# MCU.net
KiCad netlist of a schematic drawn in Altium Designer
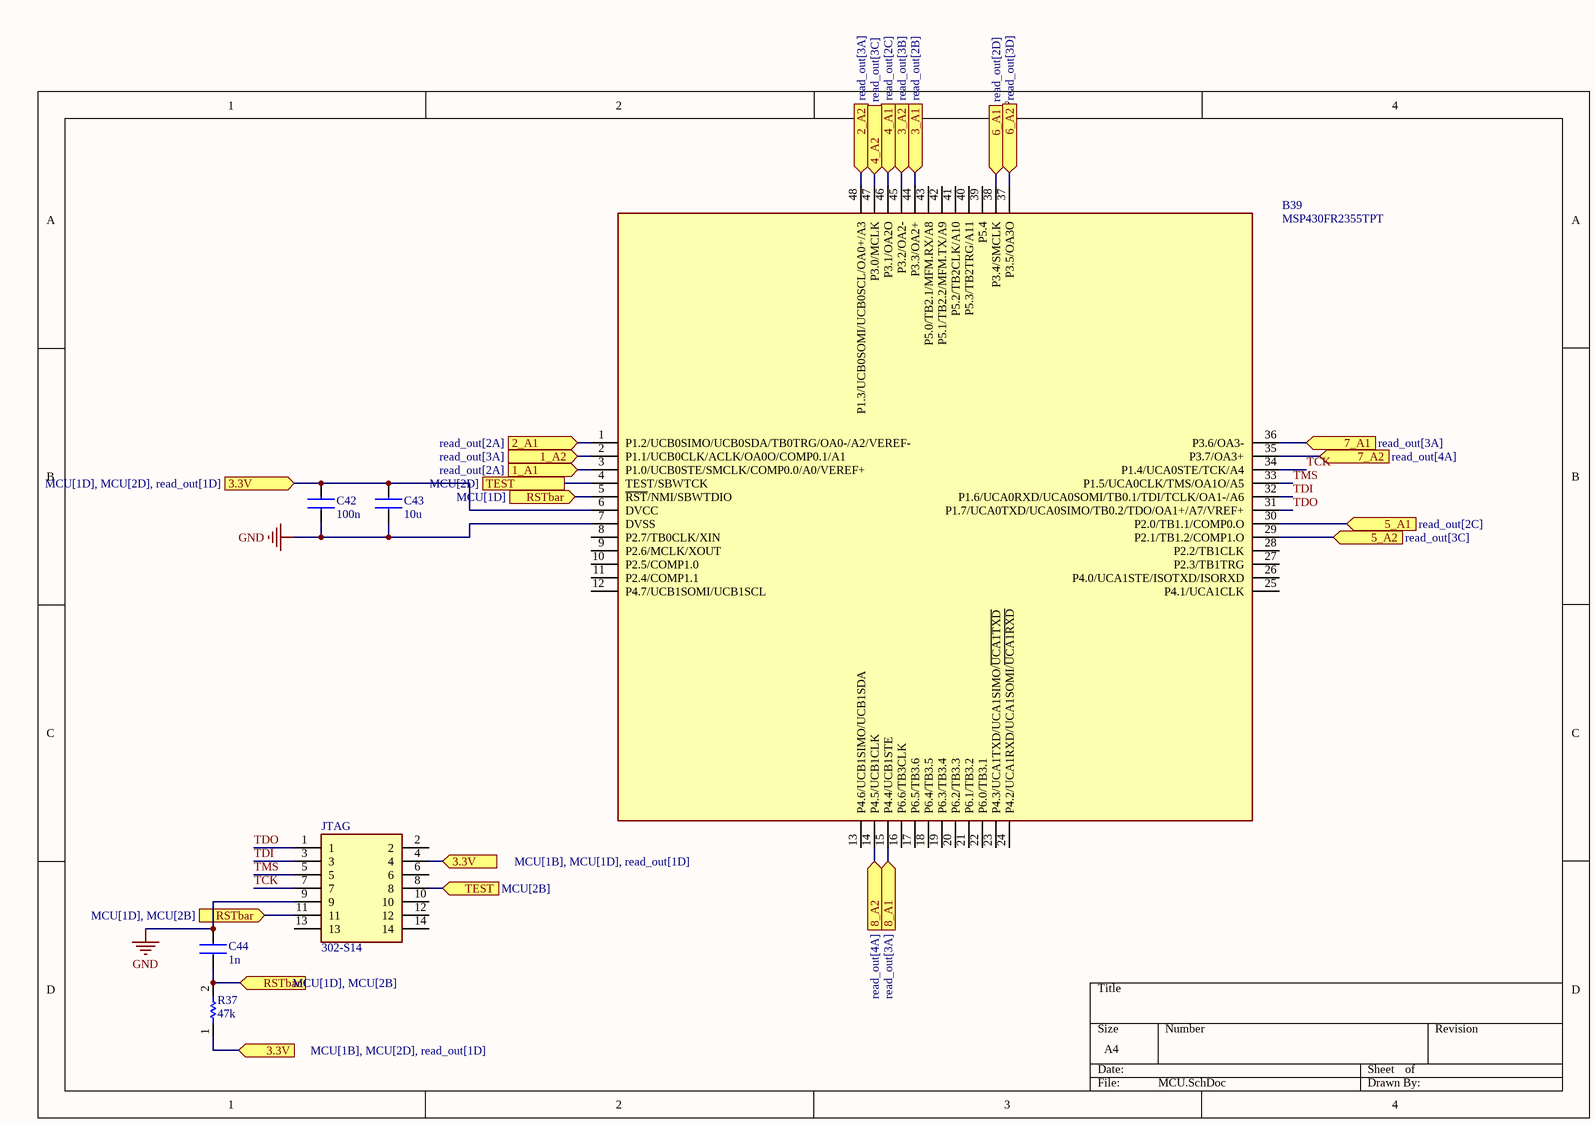
[diagram p0: MCU.SchDoc]

(export (version "E")
  (design (tool "Eeschema 10.0.6"))
  (components
    (comp (ref "B39")
      (value "MSP430FR2355TPT")
      (footprint "QFP50P900X900X160-48N")
      (fields (field (name "MOUSER PART NUMBER") "595-MSP430FR2355TPT"))
      (libsource (lib "Schlib1") (part "MSP430FR2355TPT"))
    )
    (comp (ref "C42")
      (value "100n")
      (footprint "0805X7R106KT1AT")
      (libsource (lib "Schlib1") (part "capacitor"))
    )
    (comp (ref "C43")
      (value "10u")
      (footprint "0805X7R106KT1AT")
      (libsource (lib "Schlib1") (part "capacitor"))
    )
    (comp (ref "C44")
      (value "1n")
      (footprint "0805X7R106KT1AT")
      (libsource (lib "Schlib1") (part "capacitor"))
    )
    (comp (ref "JTAG")
      (value "302-S14")
      (footprint "CONN_7024614xx_MOL")
      (libsource (lib "Schlib1") (part "JTAG"))
    )
    (comp (ref "R37")
      (value "47k")
      (footprint "CR0805-FX-1543ELF")
      (libsource (lib "Schlib1") (part "resistor"))
    )
  )
  (nets
    (net (code "1") (name "/1_A1") (class "Default")
      (node (ref "B39") (pin "3") (pinfunction "P1.0/UCB0STE/SMCLK/COMP0.0/A0/VEREF+_3") (pintype "passive"))
    )
    (net (code "2") (name "/1_A2") (class "Default")
      (node (ref "B39") (pin "2") (pinfunction "P1.1/UCB0CLK/ACLK/OA0O/COMP0.1/A1_2") (pintype "passive"))
    )
    (net (code "3") (name "/2_A1") (class "Default")
      (node (ref "B39") (pin "1") (pinfunction "P1.2/UCB0SIMO/UCB0SDA/TB0TRG/OA0-/A2/VEREF-_1") (pintype "passive"))
    )
    (net (code "4") (name "/2_A2") (class "Default")
      (node (ref "B39") (pin "48") (pinfunction "P1.3/UCB0SOMI/UCB0SCL/OA0+/A3_48") (pintype "passive"))
    )
    (net (code "5") (name "/3.3V") (class "Default")
      (node (ref "B39") (pin "6") (pinfunction "DVCC_6") (pintype "passive"))
      (node (ref "C42") (pin "1") (pinfunction "1_1") (pintype "passive"))
      (node (ref "C43") (pin "1") (pinfunction "1_1") (pintype "passive"))
      (node (ref "JTAG") (pin "4") (pinfunction "4_4") (pintype "passive"))
      (node (ref "R37") (pin "1") (pinfunction "1_1") (pintype "passive"))
    )
    (net (code "6") (name "/3_A1") (class "Default")
      (node (ref "B39") (pin "44") (pinfunction "P3.3/OA2+_44") (pintype "passive"))
    )
    (net (code "7") (name "/3_A2") (class "Default")
      (node (ref "B39") (pin "45") (pinfunction "P3.2/OA2-_45") (pintype "passive"))
    )
    (net (code "8") (name "/4_A1") (class "Default")
      (node (ref "B39") (pin "46") (pinfunction "P3.1/OA2O_46") (pintype "passive"))
    )
    (net (code "9") (name "/4_A2") (class "Default")
      (node (ref "B39") (pin "47") (pinfunction "P3.0/MCLK_47") (pintype "passive"))
    )
    (net (code "10") (name "/5_A1") (class "Default")
      (node (ref "B39") (pin "30") (pinfunction "P2.0/TB1.1/COMP0.O_30") (pintype "passive"))
    )
    (net (code "11") (name "/5_A2") (class "Default")
      (node (ref "B39") (pin "29") (pinfunction "P2.1/TB1.2/COMP1.O_29") (pintype "passive"))
    )
    (net (code "12") (name "/6_A1") (class "Default")
      (node (ref "B39") (pin "38") (pinfunction "P3.4/SMCLK_38") (pintype "passive"))
    )
    (net (code "13") (name "/6_A2") (class "Default")
      (node (ref "B39") (pin "37") (pinfunction "P3.5/OA3O_37") (pintype "passive"))
    )
    (net (code "14") (name "/7_A1") (class "Default")
      (node (ref "B39") (pin "36") (pinfunction "P3.6/OA3-_36") (pintype "passive"))
    )
    (net (code "15") (name "/7_A2") (class "Default")
      (node (ref "B39") (pin "35") (pinfunction "P3.7/OA3+_35") (pintype "passive"))
    )
    (net (code "16") (name "/8_A1") (class "Default")
      (node (ref "B39") (pin "15") (pinfunction "P4.4/UCB1STE_15") (pintype "passive"))
    )
    (net (code "17") (name "/8_A2") (class "Default")
      (node (ref "B39") (pin "14") (pinfunction "P4.5/UCB1CLK_14") (pintype "passive"))
    )
    (net (code "18") (name "/RSTbar") (class "Default")
      (node (ref "B39") (pin "5") (pinfunction "~{RST}/NMI/SBWTDIO_5") (pintype "passive"))
      (node (ref "C44") (pin "1") (pinfunction "1_1") (pintype "passive"))
      (node (ref "JTAG") (pin "11") (pinfunction "11_11") (pintype "passive"))
      (node (ref "R37") (pin "2") (pinfunction "2_2") (pintype "passive"))
    )
    (net (code "19") (name "/TCK") (class "Default")
      (node (ref "B39") (pin "34") (pinfunction "P1.4/UCA0STE/TCK/A4_34") (pintype "passive"))
      (node (ref "JTAG") (pin "7") (pinfunction "7_7") (pintype "passive"))
    )
    (net (code "20") (name "/TDI") (class "Default")
      (node (ref "B39") (pin "32") (pinfunction "P1.6/UCA0RXD/UCA0SOMI/TB0.1/TDI/TCLK/OA1-/A6_32") (pintype "passive"))
      (node (ref "JTAG") (pin "3") (pinfunction "3_3") (pintype "passive"))
    )
    (net (code "21") (name "/TDO") (class "Default")
      (node (ref "B39") (pin "31") (pinfunction "P1.7/UCA0TXD/UCA0SIMO/TB0.2/TDO/OA1+/A7/VREF+_31") (pintype "passive"))
      (node (ref "JTAG") (pin "1") (pinfunction "1_1") (pintype "passive"))
    )
    (net (code "22") (name "/TEST") (class "Default")
      (node (ref "B39") (pin "4") (pinfunction "TEST/SBWTCK_4") (pintype "passive"))
      (node (ref "JTAG") (pin "8") (pinfunction "8_8") (pintype "passive"))
    )
    (net (code "23") (name "/TMS") (class "Default")
      (node (ref "B39") (pin "33") (pinfunction "P1.5/UCA0CLK/TMS/OA1O/A5_33") (pintype "passive"))
      (node (ref "JTAG") (pin "5") (pinfunction "5_5") (pintype "passive"))
    )
    (net (code "24") (name "GND") (class "Default")
      (node (ref "B39") (pin "7") (pinfunction "DVSS_7") (pintype "passive"))
      (node (ref "C42") (pin "2") (pinfunction "2_2") (pintype "passive"))
      (node (ref "C43") (pin "2") (pinfunction "2_2") (pintype "passive"))
      (node (ref "C44") (pin "2") (pinfunction "2_2") (pintype "passive"))
      (node (ref "JTAG") (pin "9") (pinfunction "9_9") (pintype "passive"))
    )
    (net (code "25") (name "unconnected-(B39-P2.2{slash}TB1CLK-Pad28)") (class "Default")
      (node (ref "B39") (pin "28") (pinfunction "P2.2/TB1CLK_28") (pintype "passive"))
    )
    (net (code "26") (name "unconnected-(B39-P2.3{slash}TB1TRG-Pad27)") (class "Default")
      (node (ref "B39") (pin "27") (pinfunction "P2.3/TB1TRG_27") (pintype "passive"))
    )
    (net (code "27") (name "unconnected-(B39-P2.4{slash}COMP1.1-Pad11)") (class "Default")
      (node (ref "B39") (pin "11") (pinfunction "P2.4/COMP1.1_11") (pintype "passive"))
    )
    (net (code "28") (name "unconnected-(B39-P2.5{slash}COMP1.0-Pad10)") (class "Default")
      (node (ref "B39") (pin "10") (pinfunction "P2.5/COMP1.0_10") (pintype "passive"))
    )
    (net (code "29") (name "unconnected-(B39-P2.6{slash}MCLK{slash}XOUT-Pad9)") (class "Default")
      (node (ref "B39") (pin "9") (pinfunction "P2.6/MCLK/XOUT_9") (pintype "passive"))
    )
    (net (code "30") (name "unconnected-(B39-P2.7{slash}TB0CLK{slash}XIN-Pad8)") (class "Default")
      (node (ref "B39") (pin "8") (pinfunction "P2.7/TB0CLK/XIN_8") (pintype "passive"))
    )
    (net (code "31") (name "unconnected-(B39-P4.0{slash}UCA1STE{slash}ISOTXD{slash}ISORXD-Pad26)") (class "Default")
      (node (ref "B39") (pin "26") (pinfunction "P4.0/UCA1STE/ISOTXD/ISORXD_26") (pintype "passive"))
    )
    (net (code "32") (name "unconnected-(B39-P4.1{slash}UCA1CLK-Pad25)") (class "Default")
      (node (ref "B39") (pin "25") (pinfunction "P4.1/UCA1CLK_25") (pintype "passive"))
    )
    (net (code "33") (name "unconnected-(B39-P4.2{slash}UCA1RXD{slash}UCA1SOMI{slash}~{UCA1RXD}-Pad24)") (class "Default")
      (node (ref "B39") (pin "24") (pinfunction "P4.2/UCA1RXD/UCA1SOMI/~{UCA1RXD}_24") (pintype "passive"))
    )
    (net (code "34") (name "unconnected-(B39-P4.3{slash}UCA1TXD{slash}UCA1SIMO{slash}~{UCA1TXD}-Pad23)") (class "Default")
      (node (ref "B39") (pin "23") (pinfunction "P4.3/UCA1TXD/UCA1SIMO/~{UCA1TXD}_23") (pintype "passive"))
    )
    (net (code "35") (name "unconnected-(B39-P4.6{slash}UCB1SIMO{slash}UCB1SDA-Pad13)") (class "Default")
      (node (ref "B39") (pin "13") (pinfunction "P4.6/UCB1SIMO/UCB1SDA_13") (pintype "passive"))
    )
    (net (code "36") (name "unconnected-(B39-P4.7{slash}UCB1SOMI{slash}UCB1SCL-Pad12)") (class "Default")
      (node (ref "B39") (pin "12") (pinfunction "P4.7/UCB1SOMI/UCB1SCL_12") (pintype "passive"))
    )
    (net (code "37") (name "unconnected-(B39-P5.0{slash}TB2.1{slash}MFM.RX{slash}A8-Pad43)") (class "Default")
      (node (ref "B39") (pin "43") (pinfunction "P5.0/TB2.1/MFM.RX/A8_43") (pintype "passive"))
    )
    (net (code "38") (name "unconnected-(B39-P5.1{slash}TB2.2{slash}MFM.TX{slash}A9-Pad42)") (class "Default")
      (node (ref "B39") (pin "42") (pinfunction "P5.1/TB2.2/MFM.TX/A9_42") (pintype "passive"))
    )
    (net (code "39") (name "unconnected-(B39-P5.2{slash}TB2CLK{slash}A10-Pad41)") (class "Default")
      (node (ref "B39") (pin "41") (pinfunction "P5.2/TB2CLK/A10_41") (pintype "passive"))
    )
    (net (code "40") (name "unconnected-(B39-P5.3{slash}TB2TRG{slash}A11-Pad40)") (class "Default")
      (node (ref "B39") (pin "40") (pinfunction "P5.3/TB2TRG/A11_40") (pintype "passive"))
    )
    (net (code "41") (name "unconnected-(B39-P5.4-Pad39)") (class "Default")
      (node (ref "B39") (pin "39") (pinfunction "P5.4_39") (pintype "passive"))
    )
    (net (code "42") (name "unconnected-(B39-P6.0{slash}TB3.1-Pad22)") (class "Default")
      (node (ref "B39") (pin "22") (pinfunction "P6.0/TB3.1_22") (pintype "passive"))
    )
    (net (code "43") (name "unconnected-(B39-P6.1{slash}TB3.2-Pad21)") (class "Default")
      (node (ref "B39") (pin "21") (pinfunction "P6.1/TB3.2_21") (pintype "passive"))
    )
    (net (code "44") (name "unconnected-(B39-P6.2{slash}TB3.3-Pad20)") (class "Default")
      (node (ref "B39") (pin "20") (pinfunction "P6.2/TB3.3_20") (pintype "passive"))
    )
    (net (code "45") (name "unconnected-(B39-P6.3{slash}TB3.4-Pad19)") (class "Default")
      (node (ref "B39") (pin "19") (pinfunction "P6.3/TB3.4_19") (pintype "passive"))
    )
    (net (code "46") (name "unconnected-(B39-P6.4{slash}TB3.5-Pad18)") (class "Default")
      (node (ref "B39") (pin "18") (pinfunction "P6.4/TB3.5_18") (pintype "passive"))
    )
    (net (code "47") (name "unconnected-(B39-P6.5{slash}TB3.6-Pad17)") (class "Default")
      (node (ref "B39") (pin "17") (pinfunction "P6.5/TB3.6_17") (pintype "passive"))
    )
    (net (code "48") (name "unconnected-(B39-P6.6{slash}TB3CLK-Pad16)") (class "Default")
      (node (ref "B39") (pin "16") (pinfunction "P6.6/TB3CLK_16") (pintype "passive"))
    )
    (net (code "49") (name "unconnected-(JTAG-Pad2)") (class "Default")
      (node (ref "JTAG") (pin "2") (pinfunction "2_2") (pintype "passive"))
    )
    (net (code "50") (name "unconnected-(JTAG-Pad6)") (class "Default")
      (node (ref "JTAG") (pin "6") (pinfunction "6_6") (pintype "passive"))
    )
    (net (code "51") (name "unconnected-(JTAG-Pad10)") (class "Default")
      (node (ref "JTAG") (pin "10") (pinfunction "10_10") (pintype "passive"))
    )
    (net (code "52") (name "unconnected-(JTAG-Pad12)") (class "Default")
      (node (ref "JTAG") (pin "12") (pinfunction "12_12") (pintype "passive"))
    )
    (net (code "53") (name "unconnected-(JTAG-Pad13)") (class "Default")
      (node (ref "JTAG") (pin "13") (pinfunction "13_13") (pintype "passive"))
    )
    (net (code "54") (name "unconnected-(JTAG-Pad14)") (class "Default")
      (node (ref "JTAG") (pin "14") (pinfunction "14_14") (pintype "passive"))
    )
  )
)
